# DCDC.net
KiCad netlist of a schematic drawn in Altium Designer
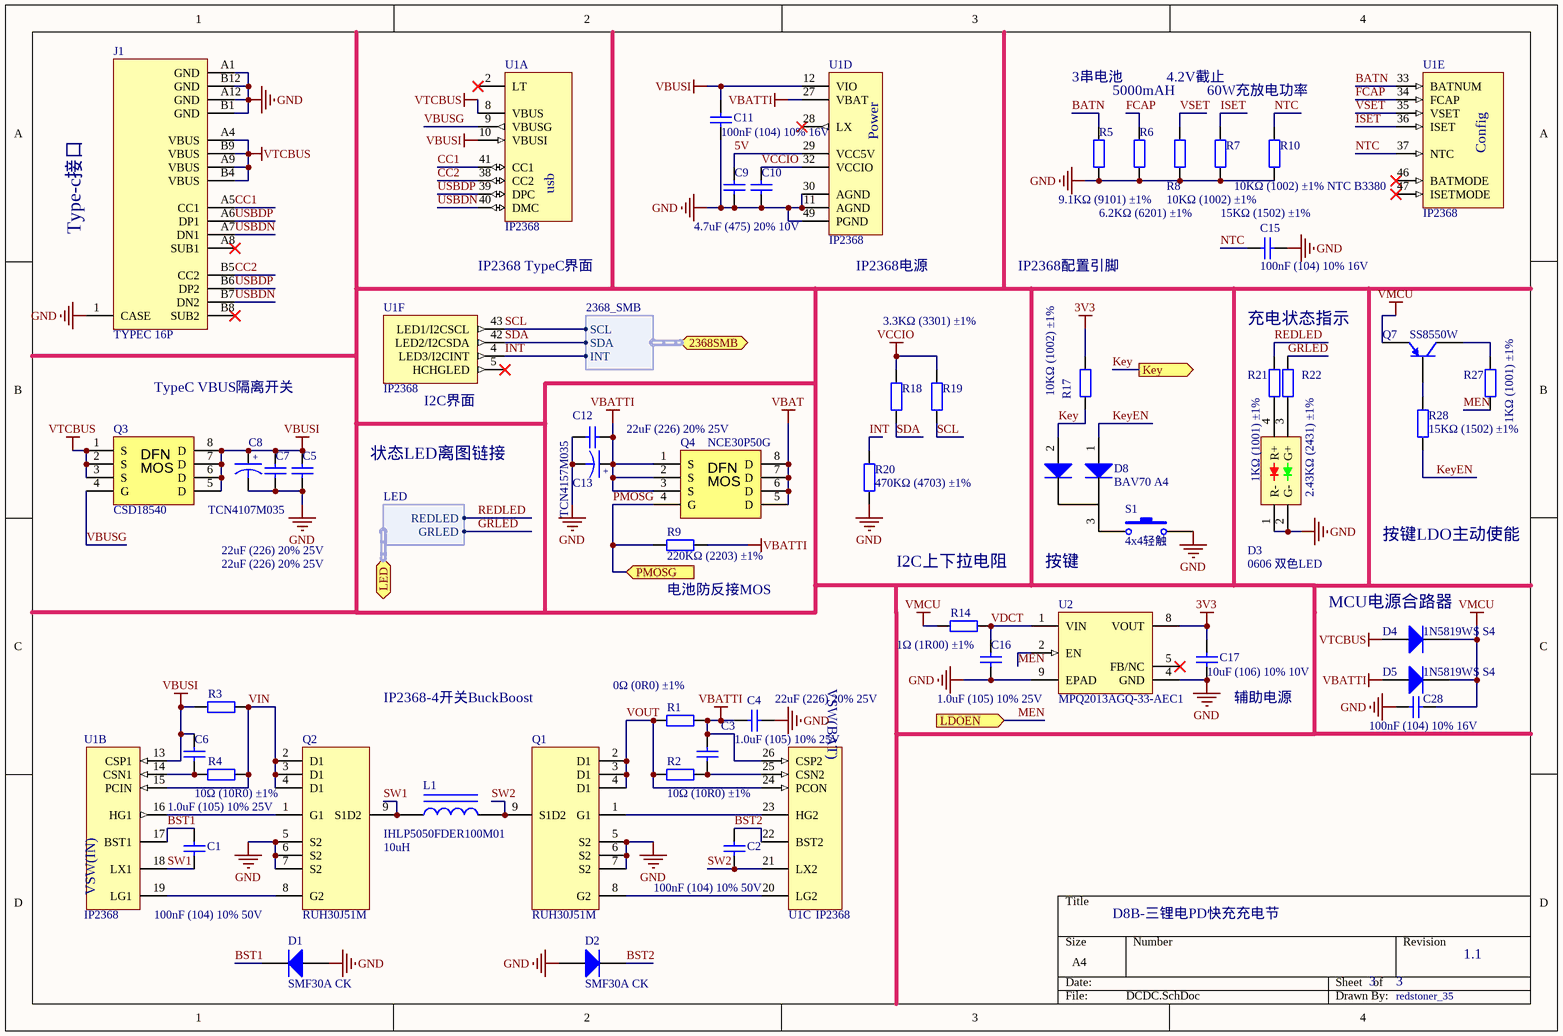
[diagram p0: DCDC.SchDoc]

(export (version "E")
  (design (tool "Eeschema 10.0.6"))
  (components
    (comp (ref "C1")
      (value "100nF (104) 10% 50V")
      (footprint "0603_C")
      (description "贴片电容")
      (libsource (lib "Miscellaneous Devices LC") (part "0603 100nF (104) 10% 50V"))
    )
    (comp (ref "C2")
      (value "100nF (104) 10% 50V")
      (footprint "0603_C")
      (description "贴片电容")
      (libsource (lib "Miscellaneous Devices LC") (part "0603 100nF (104) 10% 50V"))
    )
    (comp (ref "C3")
      (value "1.0uF (105) 10% 25V")
      (footprint "0402_C")
      (description "贴片电容")
      (libsource (lib "Miscellaneous Devices LC") (part "0402 1.0uF (105) 10% 25V"))
    )
    (comp (ref "C4")
      (value "22uF (226) 20% 25V")
      (footprint "0805_C")
      (description "贴片电容")
      (libsource (lib "Miscellaneous Devices LC") (part "0805 22uF (226) 20% 25V"))
    )
    (comp (ref "C5")
      (value "22uF (226) 20% 25V")
      (footprint "0805_C")
      (description "贴片电容")
      (libsource (lib "Miscellaneous Devices LC") (part "0805 22uF (226) 20% 25V"))
    )
    (comp (ref "C6")
      (value "1.0uF (105) 10% 25V")
      (footprint "0402_C")
      (description "贴片电容")
      (libsource (lib "Miscellaneous Devices LC") (part "0402 1.0uF (105) 10% 25V"))
    )
    (comp (ref "C7")
      (value "22uF (226) 20% 25V")
      (footprint "0805_C")
      (description "贴片电容")
      (libsource (lib "Miscellaneous Devices LC") (part "0805 22uF (226) 20% 25V"))
    )
    (comp (ref "C8")
      (value "TCN4107M035")
      (footprint "TCN4")
      (description "Capacitor")
      (libsource (lib "山猫的集成库20190318") (part "CAP2"))
    )
    (comp (ref "C9")
      (value "4.7uF (475) 20% 10V")
      (footprint "0402_C")
      (description "贴片电容")
      (libsource (lib "Miscellaneous Devices LC") (part "0402 4.7uF (475) 20% 10V"))
    )
    (comp (ref "C10")
      (value "4.7uF (475) 20% 10V")
      (footprint "0402_C")
      (description "贴片电容")
      (libsource (lib "Miscellaneous Devices LC") (part "0402 4.7uF (475) 20% 10V"))
    )
    (comp (ref "C11")
      (value "100nF (104) 10% 16V")
      (footprint "0402_C")
      (description "贴片电容")
      (libsource (lib "Miscellaneous Devices LC") (part "0402 100nF (104) 10% 16V"))
    )
    (comp (ref "C12")
      (value "22uF (226) 20% 25V")
      (footprint "0805_C")
      (description "贴片电容")
      (libsource (lib "Miscellaneous Devices LC") (part "0805 22uF (226) 20% 25V"))
    )
    (comp (ref "C13")
      (value "TCN4157M035")
      (footprint "TCN4")
      (description "Capacitor")
      (libsource (lib "山猫的集成库20190318") (part "CAP2"))
    )
    (comp (ref "C15")
      (value "100nF (104) 10% 16V")
      (footprint "0402_C")
      (description "贴片电容")
      (libsource (lib "Miscellaneous Devices LC") (part "0402 100nF (104) 10% 16V"))
    )
    (comp (ref "C16")
      (value "1.0uF (105) 10% 25V")
      (footprint "0402_C")
      (description "贴片电容")
      (libsource (lib "Miscellaneous Devices LC") (part "0402 1.0uF (105) 10% 25V"))
    )
    (comp (ref "C17")
      (value "10uF (106) 10% 10V")
      (footprint "0603_C")
      (description "贴片电容")
      (libsource (lib "Miscellaneous Devices LC") (part "0603 10uF (106) 10% 10V"))
    )
    (comp (ref "C28")
      (value "100nF (104) 10% 16V")
      (footprint "0402_C")
      (description "贴片电容")
      (libsource (lib "Miscellaneous Devices LC") (part "0402 100nF (104) 10% 16V"))
    )
    (comp (ref "D1")
      (value "SMF30A CK")
      (footprint "SOD-123")
      (description "TVS二极管")
      (libsource (lib "Miscellaneous Devices LC") (part "SOD-123 B5819W  SL"))
    )
    (comp (ref "D2")
      (value "SMF30A CK")
      (footprint "SOD-123")
      (description "TVS二极管")
      (libsource (lib "Miscellaneous Devices LC") (part "SOD-123 B5819W  SL"))
    )
    (comp (ref "D3")
      (value "0606 双色LED")
      (footprint "LED-SMD_4P-L1.6-W1.5-TL-1")
      (description "0606 双色LED 红色/翠绿")
      (libsource (lib "custom") (part "0606DualColor LED"))
    )
    (comp (ref "D4")
      (value "1N5819WS S4")
      (footprint "SOD-323")
      (description "二极管")
      (libsource (lib "Miscellaneous Devices LC") (part "SOD-323 1N4148WS T4"))
    )
    (comp (ref "D5")
      (value "1N5819WS S4")
      (footprint "SOD-323")
      (description "二极管")
      (libsource (lib "Miscellaneous Devices LC") (part "SOD-323 1N4148WS T4"))
    )
    (comp (ref "D8")
      (value "BAV70 A4")
      (footprint "SC70-3")
      (description "开关二极管")
      (libsource (lib "Miscellaneous Devices LC") (part "SOT-23 BAV70 A4"))
    )
    (comp (ref "J1")
      (value "TYPEC 16P")
      (footprint "USB-C-SMD_KH-TYPE-C-16P")
      (description "16Pin TypeC立贴座子")
      (libsource (lib "custom") (part "KH-TYPEC-16P"))
    )
    (comp (ref "L1")
      (value "IHLP5050FDER100M01")
      (footprint "IHLP5050FDER***M01")
      (description "Vishay Inductor 10uH 16.4mR 15.5A")
      (fields (field (name "ALTIUM_VALUE") "10uH") (field (name "PUBLISHER") "Altium Limited"))
      (libsource (lib "Miscellaneous Devices") (part "Inductor Iron"))
    )
    (comp (ref "Q1")
      (value "RUH30J51M")
      (footprint "PDFN-8_L5.8-W4.9_RU30J30M")
      (description "Dual N MOSFET 30V/51A")
      (libsource (lib "custom") (part "RU30J30M"))
    )
    (comp (ref "Q2")
      (value "RUH30J51M")
      (footprint "PDFN-8_L5.8-W4.9_RU30J30M")
      (description "Dual N MOSFET 30V/51A")
      (libsource (lib "") (part "RU30J30M_1"))
    )
    (comp (ref "Q3")
      (value "CSD18540")
      (footprint "SON/DFN5x6(MOS)")
      (description "Gerenal DFN/SON Package MOSFET")
      (libsource (lib "custom") (part "SON/DFN5x6 MOS"))
    )
    (comp (ref "Q4")
      (value "NCE30P50G")
      (footprint "SON/DFN5x6(MOS)")
      (description "Gerenal DFN/SON Package MOSFET")
      (libsource (lib "custom") (part "SON/DFN5x6 MOS"))
    )
    (comp (ref "Q7")
      (value "SS8550W")
      (footprint "SC70-3")
      (description "三极管")
      (libsource (lib "Miscellaneous Devices LC") (part "SOT-23 SS8550 Y2"))
    )
    (comp (ref "R1")
      (value "0Ω (0R0) ±1%")
      (footprint "1206_R")
      (description "贴片电阻")
      (libsource (lib "Miscellaneous Devices LC") (part "1206 0Ω (0R0) 1%"))
    )
    (comp (ref "R2")
      (value "10Ω (10R0) ±1%")
      (footprint "0402_R")
      (description "贴片电阻")
      (libsource (lib "Miscellaneous Devices LC") (part "0402 10Ω (10R0) 1%"))
    )
    (comp (ref "R3")
      (value "0Ω (0R0) ±1%")
      (footprint "1206_R")
      (description "贴片电阻")
      (libsource (lib "Miscellaneous Devices LC") (part "1206 0Ω (0R0) 1%"))
    )
    (comp (ref "R4")
      (value "10Ω (10R0) ±1%")
      (footprint "0402_R")
      (description "贴片电阻")
      (libsource (lib "Miscellaneous Devices LC") (part "0402 10Ω (10R0) 1%"))
    )
    (comp (ref "R5")
      (value "9.1KΩ (9101) ±1%")
      (footprint "0402_R")
      (description "贴片电阻")
      (libsource (lib "Miscellaneous Devices LC") (part "0402 0Ω (0R0) 1%"))
    )
    (comp (ref "R6")
      (value "6.2KΩ (6201) ±1%")
      (footprint "0402_R")
      (description "贴片电阻")
      (libsource (lib "Miscellaneous Devices LC") (part "0402 0Ω (0R0) 1%"))
    )
    (comp (ref "R7")
      (value "15KΩ (1502) ±1%")
      (footprint "0402_R")
      (description "贴片电阻")
      (libsource (lib "Miscellaneous Devices LC") (part "0402 15KΩ (1502) 1%"))
    )
    (comp (ref "R8")
      (value "10KΩ (1002) ±1%")
      (footprint "0402_R")
      (description "贴片电阻")
      (libsource (lib "Miscellaneous Devices LC") (part "0402 10KΩ (1002) 1%"))
    )
    (comp (ref "R9")
      (value "220KΩ (2203) ±1%")
      (footprint "0402_R")
      (description "贴片电阻")
      (libsource (lib "Miscellaneous Devices LC") (part "0402 220KΩ (2203) 1%"))
    )
    (comp (ref "R10")
      (value "10KΩ (1002) ±1% NTC B3380")
      (footprint "0402_R")
      (description "贴片NTC热敏电阻")
      (libsource (lib "Miscellaneous Devices LC") (part "0402 10KΩ (1002) 1%"))
    )
    (comp (ref "R14")
      (value "1Ω (1R00) ±1%")
      (footprint "0402_R")
      (description "贴片电阻")
      (libsource (lib "Miscellaneous Devices LC") (part "0402 1Ω (1R00) 1%"))
    )
    (comp (ref "R17")
      (value "10KΩ (1002) ±1%")
      (footprint "0402_R")
      (description "贴片电阻")
      (libsource (lib "Miscellaneous Devices LC") (part "0402 10KΩ (1002) 1%"))
    )
    (comp (ref "R18")
      (value "3.3KΩ (3301) ±1%")
      (footprint "0402_R")
      (description "贴片电阻")
      (libsource (lib "Miscellaneous Devices LC") (part "0402 3.3KΩ (3301) 1%"))
    )
    (comp (ref "R19")
      (value "3.3KΩ (3301) ±1%")
      (footprint "0402_R")
      (description "贴片电阻")
      (libsource (lib "Miscellaneous Devices LC") (part "0402 3.3KΩ (3301) 1%"))
    )
    (comp (ref "R20")
      (value "470KΩ (4703) ±1%")
      (footprint "0402_R")
      (description "贴片电阻")
      (libsource (lib "Miscellaneous Devices LC") (part "0402 470KΩ (4703) 1%"))
    )
    (comp (ref "R21")
      (value "1KΩ (1001) ±1%")
      (footprint "0402_R")
      (description "贴片电阻")
      (libsource (lib "Miscellaneous Devices LC") (part "0402 1KΩ (1001) 1%"))
    )
    (comp (ref "R22")
      (value "2.43KΩ (2431) ±1%")
      (footprint "0402_R")
      (description "贴片电阻")
      (libsource (lib "Miscellaneous Devices LC") (part "0402 2KΩ (2001) 1%"))
    )
    (comp (ref "R27")
      (value "1KΩ (1001) ±1%")
      (footprint "0402_R")
      (description "贴片电阻")
      (libsource (lib "Miscellaneous Devices LC") (part "0402 1KΩ (1001) 1%"))
    )
    (comp (ref "R28")
      (value "15KΩ (1502) ±1%")
      (footprint "0402_R")
      (description "贴片电阻")
      (libsource (lib "Miscellaneous Devices LC") (part "0402 15KΩ (1502) 1%"))
    )
    (comp (ref "S1")
      (value "4x4轻触")
      (footprint "SW-SMD_4P-L5.2-W5.2-P3.70-LS6.4")
      (description "Switch")
      (fields (field (name "PUBLISHER") "Altium Limited"))
      (libsource (lib "Miscellaneous Devices") (part "SW-PB"))
    )
    (comp (ref "U1")
      (value "IP2368")
      (footprint "QFN50P700X700X100_HS-49M")
      (description "IP2368 2-5S 双向电池充放电管理，100W PD")
      (libsource (lib "custom") (part "IP2368"))
    )
    (comp (ref "U2")
      (value "MPQ2013AGQ-33-AEC1")
      (footprint "MPQ2013A-QFN8")
      (description "MPS 40V LDO with Enable pin QFN3x3 package")
      (libsource (lib "custom") (part "MPQ2013AGQ-xx-AEC1"))
    )
  )
  (nets
    (net (code "3") (name "/5V") (class "Default")
      (node (ref "C9") (pin "2") (pinfunction "2_2") (pintype "passive"))
      (node (ref "U1") (pin "29") (pinfunction "VCC5V_29") (pintype "power_in"))
    )
    (net (code "4") (name "/BATN") (class "Default")
      (node (ref "R5") (pin "2") (pinfunction "2_2") (pintype "passive"))
      (node (ref "U1") (pin "33") (pinfunction "BATNUM_33") (pintype "input"))
    )
    (net (code "5") (name "/BST1") (class "Default")
      (node (ref "C1") (pin "2") (pinfunction "2_2") (pintype "passive"))
      (node (ref "D1") (pin "2") (pinfunction "K_2") (pintype "passive"))
      (node (ref "U1") (pin "17") (pinfunction "BST1_17") (pintype "power_in"))
    )
    (net (code "6") (name "/BST2") (class "Default")
      (node (ref "C2") (pin "2") (pinfunction "2_2") (pintype "passive"))
      (node (ref "D2") (pin "2") (pinfunction "K_2") (pintype "passive"))
      (node (ref "U1") (pin "22") (pinfunction "BST2_22") (pintype "power_in"))
    )
    (net (code "7") (name "/CC1") (class "Default")
      (node (ref "J1") (pin "A5") (pinfunction "CC1_A5") (pintype "passive"))
      (node (ref "U1") (pin "41") (pinfunction "CC1_41") (pintype "bidirectional"))
    )
    (net (code "8") (name "/CC2") (class "Default")
      (node (ref "J1") (pin "B5") (pinfunction "CC2_B5") (pintype "passive"))
      (node (ref "U1") (pin "38") (pinfunction "CC2_38") (pintype "bidirectional"))
    )
    (net (code "9") (name "/FCAP") (class "Default")
      (node (ref "R6") (pin "2") (pinfunction "2_2") (pintype "passive"))
      (node (ref "U1") (pin "34") (pinfunction "FCAP_34") (pintype "input"))
    )
    (net (code "10") (name "/GRLED") (class "Default")
      (node (ref "R22") (pin "1") (pinfunction "1_1") (pintype "passive"))
    )
    (net (code "11") (name "/INT") (class "Default")
      (node (ref "R20") (pin "2") (pinfunction "2_2") (pintype "passive"))
      (node (ref "U1") (pin "4") (pinfunction "LED3/I2CINT_4") (pintype "output"))
    )
    (net (code "12") (name "/ISET") (class "Default")
      (node (ref "R7") (pin "2") (pinfunction "2_2") (pintype "passive"))
      (node (ref "U1") (pin "36") (pinfunction "ISET_36") (pintype "input"))
    )
    (net (code "13") (name "/Key") (class "Default")
      (node (ref "D8") (pin "2") (pinfunction "A_2") (pintype "passive"))
      (node (ref "R17") (pin "1") (pinfunction "1_1") (pintype "passive"))
    )
    (net (code "14") (name "/KeyEN") (class "Default")
      (node (ref "D8") (pin "1") (pinfunction "A_1") (pintype "passive"))
      (node (ref "R28") (pin "1") (pinfunction "1_1") (pintype "passive"))
    )
    (net (code "15") (name "/MEN") (class "Default")
      (node (ref "R27") (pin "1") (pinfunction "1_1") (pintype "passive"))
      (node (ref "U2") (pin "2") (pinfunction "EN_2") (pintype "input"))
    )
    (net (code "16") (name "/NTC") (class "Default")
      (node (ref "C15") (pin "1") (pinfunction "1_1") (pintype "passive"))
      (node (ref "R10") (pin "2") (pinfunction "2_2") (pintype "passive"))
      (node (ref "U1") (pin "37") (pinfunction "NTC_37") (pintype "input"))
    )
    (net (code "17") (name "/PMOSG") (class "Default")
      (node (ref "Q4") (pin "4") (pinfunction "G_4") (pintype "passive"))
      (node (ref "R9") (pin "1") (pinfunction "1_1") (pintype "passive"))
    )
    (net (code "18") (name "/REDLED") (class "Default")
      (node (ref "R21") (pin "2") (pinfunction "2_2") (pintype "passive"))
    )
    (net (code "19") (name "/SCL") (class "Default")
      (node (ref "R19") (pin "1") (pinfunction "1_1") (pintype "passive"))
      (node (ref "U1") (pin "43") (pinfunction "LED1/I2CSCL_43") (pintype "output"))
    )
    (net (code "20") (name "/SDA") (class "Default")
      (node (ref "R18") (pin "1") (pinfunction "1_1") (pintype "passive"))
      (node (ref "U1") (pin "42") (pinfunction "LED2/I2CSDA_42") (pintype "output"))
    )
    (net (code "21") (name "/SW1") (class "Default")
      (node (ref "C1") (pin "1") (pinfunction "1_1") (pintype "passive"))
      (node (ref "L1") (pin "1") (pinfunction "1_1") (pintype "passive"))
      (node (ref "Q2") (pin "9") (pinfunction "S1D2_9") (pintype "passive"))
      (node (ref "U1") (pin "18") (pinfunction "LX1_18") (pintype "power_in"))
    )
    (net (code "22") (name "/SW2") (class "Default")
      (node (ref "C2") (pin "1") (pinfunction "1_1") (pintype "passive"))
      (node (ref "L1") (pin "2") (pinfunction "2_2") (pintype "passive"))
      (node (ref "Q1") (pin "9") (pinfunction "S1D2_9") (pintype "passive"))
      (node (ref "U1") (pin "21") (pinfunction "LX2_21") (pintype "power_in"))
    )
    (net (code "23") (name "/USBDN") (class "Default")
      (node (ref "J1") (pin "A7") (pinfunction "DN1_A7") (pintype "passive"))
      (node (ref "J1") (pin "B7") (pinfunction "DN2_B7") (pintype "passive"))
      (node (ref "U1") (pin "40") (pinfunction "DMC_40") (pintype "bidirectional"))
    )
    (net (code "24") (name "/USBDP") (class "Default")
      (node (ref "J1") (pin "A6") (pinfunction "DP1_A6") (pintype "passive"))
      (node (ref "J1") (pin "B6") (pinfunction "DP2_B6") (pintype "passive"))
      (node (ref "U1") (pin "39") (pinfunction "DPC_39") (pintype "bidirectional"))
    )
    (net (code "25") (name "/VBUSG") (class "Default")
      (node (ref "Q3") (pin "4") (pinfunction "G_4") (pintype "passive"))
      (node (ref "U1") (pin "9") (pinfunction "VBUSG_9") (pintype "output"))
    )
    (net (code "26") (name "/VDCT") (class "Default")
      (node (ref "C16") (pin "2") (pinfunction "2_2") (pintype "passive"))
      (node (ref "R14") (pin "2") (pinfunction "2_2") (pintype "passive"))
      (node (ref "U2") (pin "1") (pinfunction "VIN_1") (pintype "power_in"))
    )
    (net (code "27") (name "/VIN") (class "Default")
      (node (ref "Q2") (pin "2") (pinfunction "D1_2") (pintype "passive"))
      (node (ref "Q2") (pin "3") (pinfunction "D1_3") (pintype "passive"))
      (node (ref "Q2") (pin "4") (pinfunction "D1_4") (pintype "passive"))
      (node (ref "R3") (pin "2") (pinfunction "2_2") (pintype "passive"))
      (node (ref "R4") (pin "2") (pinfunction "2_2") (pintype "passive"))
      (node (ref "U1") (pin "15") (pinfunction "PCIN_15") (pintype "input"))
    )
    (net (code "28") (name "/VOUT") (class "Default")
      (node (ref "Q1") (pin "2") (pinfunction "D1_2") (pintype "passive"))
      (node (ref "Q1") (pin "3") (pinfunction "D1_3") (pintype "passive"))
      (node (ref "Q1") (pin "4") (pinfunction "D1_4") (pintype "passive"))
      (node (ref "R1") (pin "1") (pinfunction "1_1") (pintype "passive"))
      (node (ref "R2") (pin "1") (pinfunction "1_1") (pintype "passive"))
      (node (ref "U1") (pin "24") (pinfunction "PCON_24") (pintype "input"))
    )
    (net (code "29") (name "/VSET") (class "Default")
      (node (ref "R8") (pin "2") (pinfunction "2_2") (pintype "passive"))
      (node (ref "U1") (pin "35") (pinfunction "VSET_35") (pintype "input"))
    )
    (net (code "32") (name "3V3") (class "Default")
      (node (ref "C17") (pin "2") (pinfunction "2_2") (pintype "passive"))
      (node (ref "R17") (pin "2") (pinfunction "2_2") (pintype "passive"))
      (node (ref "U2") (pin "8") (pinfunction "VOUT_8") (pintype "passive"))
    )
    (net (code "33") (name "GND") (class "Default")
      (node (ref "C10") (pin "1") (pinfunction "1_1") (pintype "passive"))
      (node (ref "C11") (pin "1") (pinfunction "1_1") (pintype "passive"))
      (node (ref "C12") (pin "2") (pinfunction "2_2") (pintype "passive"))
      (node (ref "C13") (pin "2") (pinfunction "2_2") (pintype "passive"))
      (node (ref "C15") (pin "2") (pinfunction "2_2") (pintype "passive"))
      (node (ref "C16") (pin "1") (pinfunction "1_1") (pintype "passive"))
      (node (ref "C17") (pin "1") (pinfunction "1_1") (pintype "passive"))
      (node (ref "C28") (pin "1") (pinfunction "1_1") (pintype "passive"))
      (node (ref "C4") (pin "2") (pinfunction "2_2") (pintype "passive"))
      (node (ref "C5") (pin "1") (pinfunction "1_1") (pintype "passive"))
      (node (ref "C7") (pin "1") (pinfunction "1_1") (pintype "passive"))
      (node (ref "C8") (pin "2") (pinfunction "2_2") (pintype "passive"))
      (node (ref "C9") (pin "1") (pinfunction "1_1") (pintype "passive"))
      (node (ref "D1") (pin "1") (pinfunction "A_1") (pintype "passive"))
      (node (ref "D2") (pin "1") (pinfunction "A_1") (pintype "passive"))
      (node (ref "D3") (pin "1") (pinfunction "R-_1") (pintype "passive"))
      (node (ref "D3") (pin "2") (pinfunction "G-_2") (pintype "passive"))
      (node (ref "J1") (pin "1") (pinfunction "CASE_1") (pintype "passive"))
      (node (ref "J1") (pin "A1") (pinfunction "GND_A1") (pintype "passive"))
      (node (ref "J1") (pin "A12") (pinfunction "GND_A12") (pintype "passive"))
      (node (ref "J1") (pin "B1") (pinfunction "GND_B1") (pintype "passive"))
      (node (ref "J1") (pin "B12") (pinfunction "GND_B12") (pintype "passive"))
      (node (ref "Q1") (pin "5") (pinfunction "S2_5") (pintype "passive"))
      (node (ref "Q1") (pin "6") (pinfunction "S2_6") (pintype "passive"))
      (node (ref "Q1") (pin "7") (pinfunction "S2_7") (pintype "passive"))
      (node (ref "Q2") (pin "5") (pinfunction "S2_5") (pintype "passive"))
      (node (ref "Q2") (pin "6") (pinfunction "S2_6") (pintype "passive"))
      (node (ref "Q2") (pin "7") (pinfunction "S2_7") (pintype "passive"))
      (node (ref "R10") (pin "1") (pinfunction "1_1") (pintype "passive"))
      (node (ref "R20") (pin "1") (pinfunction "1_1") (pintype "passive"))
      (node (ref "R5") (pin "1") (pinfunction "1_1") (pintype "passive"))
      (node (ref "R6") (pin "1") (pinfunction "1_1") (pintype "passive"))
      (node (ref "R7") (pin "1") (pinfunction "1_1") (pintype "passive"))
      (node (ref "R8") (pin "1") (pinfunction "1_1") (pintype "passive"))
      (node (ref "S1") (pin "2") (pinfunction "2_2") (pintype "passive"))
      (node (ref "U1") (pin "11") (pinfunction "AGND_11") (pintype "power_in"))
      (node (ref "U1") (pin "30") (pinfunction "AGND_30") (pintype "power_in"))
      (node (ref "U1") (pin "49") (pinfunction "PGND_49") (pintype "power_in"))
      (node (ref "U2") (pin "4") (pinfunction "GND_4") (pintype "power_in"))
      (node (ref "U2") (pin "9") (pinfunction "EPAD_9") (pintype "passive"))
    )
    (net (code "34") (name "Net-(D3-G+)") (class "Default")
      (node (ref "D3") (pin "3") (pinfunction "G+_3") (pintype "passive"))
      (node (ref "R22") (pin "2") (pinfunction "2_2") (pintype "passive"))
    )
    (net (code "35") (name "Net-(D3-R+)") (class "Default")
      (node (ref "D3") (pin "4") (pinfunction "R+_4") (pintype "passive"))
      (node (ref "R21") (pin "1") (pinfunction "1_1") (pintype "passive"))
    )
    (net (code "36") (name "Net-(D8-K)") (class "Default")
      (node (ref "D8") (pin "3") (pinfunction "K_3") (pintype "passive"))
      (node (ref "S1") (pin "1") (pinfunction "1_1") (pintype "passive"))
    )
    (net (code "37") (name "Net-(Q1-G1)") (class "Default")
      (node (ref "Q1") (pin "1") (pinfunction "G1_1") (pintype "passive"))
      (node (ref "U1") (pin "23") (pinfunction "HG2_23") (pintype "power_in"))
    )
    (net (code "38") (name "Net-(Q1-G2)") (class "Default")
      (node (ref "Q1") (pin "8") (pinfunction "G2_8") (pintype "passive"))
      (node (ref "U1") (pin "20") (pinfunction "LG2_20") (pintype "power_in"))
    )
    (net (code "39") (name "Net-(Q2-G1)") (class "Default")
      (node (ref "Q2") (pin "1") (pinfunction "G1_1") (pintype "passive"))
      (node (ref "U1") (pin "16") (pinfunction "HG1_16") (pintype "output"))
    )
    (net (code "40") (name "Net-(Q2-G2)") (class "Default")
      (node (ref "Q2") (pin "8") (pinfunction "G2_8") (pintype "passive"))
      (node (ref "U1") (pin "19") (pinfunction "LG1_19") (pintype "power_in"))
    )
    (net (code "41") (name "Net-(Q7-B)") (class "Default")
      (node (ref "Q7") (pin "1") (pinfunction "B_1") (pintype "passive"))
      (node (ref "R28") (pin "2") (pinfunction "2_2") (pintype "passive"))
    )
    (net (code "42") (name "Net-(Q7-C)") (class "Default")
      (node (ref "Q7") (pin "3") (pinfunction "C_3") (pintype "passive"))
      (node (ref "R27") (pin "2") (pinfunction "2_2") (pintype "passive"))
    )
    (net (code "43") (name "Net-(U1B-CSN1)") (class "Default")
      (node (ref "C6") (pin "1") (pinfunction "1_1") (pintype "passive"))
      (node (ref "R4") (pin "1") (pinfunction "1_1") (pintype "passive"))
      (node (ref "U1") (pin "14") (pinfunction "CSN1_14") (pintype "input"))
    )
    (net (code "44") (name "Net-(U1C-CSN2)") (class "Default")
      (node (ref "C3") (pin "1") (pinfunction "1_1") (pintype "passive"))
      (node (ref "R2") (pin "2") (pinfunction "2_2") (pintype "passive"))
      (node (ref "U1") (pin "25") (pinfunction "CSN2_25") (pintype "input"))
    )
    (net (code "45") (name "VBAT") (class "Default")
      (node (ref "Q4") (pin "5") (pinfunction "D_5") (pintype "passive"))
      (node (ref "Q4") (pin "6") (pinfunction "D_6") (pintype "passive"))
      (node (ref "Q4") (pin "7") (pinfunction "D_7") (pintype "passive"))
      (node (ref "Q4") (pin "8") (pinfunction "D_8") (pintype "passive"))
    )
    (net (code "46") (name "VBATTI") (class "Default")
      (node (ref "C12") (pin "1") (pinfunction "1_1") (pintype "passive"))
      (node (ref "C13") (pin "1") (pinfunction "1_1") (pintype "passive"))
      (node (ref "C3") (pin "2") (pinfunction "2_2") (pintype "passive"))
      (node (ref "C4") (pin "1") (pinfunction "1_1") (pintype "passive"))
      (node (ref "D5") (pin "1") (pinfunction "A_1") (pintype "passive"))
      (node (ref "Q4") (pin "1") (pinfunction "S_1") (pintype "passive"))
      (node (ref "Q4") (pin "2") (pinfunction "S_2") (pintype "passive"))
      (node (ref "Q4") (pin "3") (pinfunction "S_3") (pintype "passive"))
      (node (ref "R1") (pin "2") (pinfunction "2_2") (pintype "passive"))
      (node (ref "R9") (pin "2") (pinfunction "2_2") (pintype "passive"))
      (node (ref "U1") (pin "26") (pinfunction "CSP2_26") (pintype "input"))
      (node (ref "U1") (pin "27") (pinfunction "VBAT_27") (pintype "power_in"))
    )
    (net (code "47") (name "VBUSI") (class "Default")
      (node (ref "C11") (pin "2") (pinfunction "2_2") (pintype "passive"))
      (node (ref "C5") (pin "2") (pinfunction "2_2") (pintype "passive"))
      (node (ref "C6") (pin "2") (pinfunction "2_2") (pintype "passive"))
      (node (ref "C7") (pin "2") (pinfunction "2_2") (pintype "passive"))
      (node (ref "C8") (pin "1") (pinfunction "1_1") (pintype "passive"))
      (node (ref "Q3") (pin "5") (pinfunction "D_5") (pintype "passive"))
      (node (ref "Q3") (pin "6") (pinfunction "D_6") (pintype "passive"))
      (node (ref "Q3") (pin "7") (pinfunction "D_7") (pintype "passive"))
      (node (ref "Q3") (pin "8") (pinfunction "D_8") (pintype "passive"))
      (node (ref "R3") (pin "1") (pinfunction "1_1") (pintype "passive"))
      (node (ref "U1") (pin "10") (pinfunction "VBUSI_10") (pintype "input"))
      (node (ref "U1") (pin "12") (pinfunction "VIO_12") (pintype "power_in"))
      (node (ref "U1") (pin "13") (pinfunction "CSP1_13") (pintype "input"))
    )
    (net (code "48") (name "VCCIO") (class "Default")
      (node (ref "C10") (pin "2") (pinfunction "2_2") (pintype "passive"))
      (node (ref "R18") (pin "2") (pinfunction "2_2") (pintype "passive"))
      (node (ref "R19") (pin "2") (pinfunction "2_2") (pintype "passive"))
      (node (ref "U1") (pin "32") (pinfunction "VCCIO_32") (pintype "power_in"))
    )
    (net (code "49") (name "VMCU") (class "Default")
      (node (ref "C28") (pin "2") (pinfunction "2_2") (pintype "passive"))
      (node (ref "D4") (pin "2") (pinfunction "K_2") (pintype "passive"))
      (node (ref "D5") (pin "2") (pinfunction "K_2") (pintype "passive"))
      (node (ref "Q7") (pin "2") (pinfunction "E_2") (pintype "passive"))
      (node (ref "R14") (pin "1") (pinfunction "1_1") (pintype "passive"))
    )
    (net (code "50") (name "VTCBUS") (class "Default")
      (node (ref "D4") (pin "1") (pinfunction "A_1") (pintype "passive"))
      (node (ref "J1") (pin "A4") (pinfunction "VBUS_A4") (pintype "passive"))
      (node (ref "J1") (pin "A9") (pinfunction "VBUS_A9") (pintype "passive"))
      (node (ref "J1") (pin "B4") (pinfunction "VBUS_B4") (pintype "passive"))
      (node (ref "J1") (pin "B9") (pinfunction "VBUS_B9") (pintype "passive"))
      (node (ref "Q3") (pin "1") (pinfunction "S_1") (pintype "passive"))
      (node (ref "Q3") (pin "2") (pinfunction "S_2") (pintype "passive"))
      (node (ref "Q3") (pin "3") (pinfunction "S_3") (pintype "passive"))
      (node (ref "U1") (pin "8") (pinfunction "VBUS_8") (pintype "passive"))
    )
    (net (code "51") (name "unconnected-(J1-SUB1-PadA8)") (class "Default")
      (node (ref "J1") (pin "A8") (pinfunction "SUB1_A8") (pintype "passive+no_connect"))
    )
    (net (code "52") (name "unconnected-(J1-SUB2-PadB8)") (class "Default")
      (node (ref "J1") (pin "B8") (pinfunction "SUB2_B8") (pintype "passive+no_connect"))
    )
    (net (code "53") (name "unconnected-(U1A-LT-Pad2)") (class "Default")
      (node (ref "U1") (pin "2") (pinfunction "LT_2") (pintype "passive+no_connect"))
    )
    (net (code "54") (name "unconnected-(U1D-LX-Pad28)") (class "Default")
      (node (ref "U1") (pin "28") (pinfunction "LX_28") (pintype "output+no_connect"))
    )
    (net (code "55") (name "unconnected-(U1E-BATMODE-Pad46)") (class "Default")
      (node (ref "U1") (pin "46") (pinfunction "BATMODE_46") (pintype "input+no_connect"))
    )
    (net (code "56") (name "unconnected-(U1E-ISETMODE-Pad47)") (class "Default")
      (node (ref "U1") (pin "47") (pinfunction "ISETMODE_47") (pintype "input+no_connect"))
    )
    (net (code "57") (name "unconnected-(U1F-HCHGLED-Pad5)") (class "Default")
      (node (ref "U1") (pin "5") (pinfunction "HCHGLED_5") (pintype "output+no_connect"))
    )
    (net (code "58") (name "unconnected-(U2-FB{slash}NC-Pad5)") (class "Default")
      (node (ref "U2") (pin "5") (pinfunction "FB/NC_5") (pintype "passive+no_connect"))
    )
  )
)
